# ArduSensor-Pot.net
KiCad netlist of a schematic drawn in EAGLE
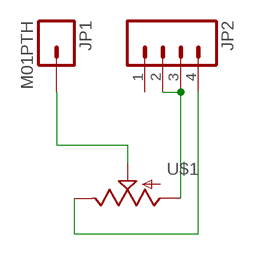
[diagram p0: schematic, sheet 1]

(export (version "E")
  (design (tool "Eeschema 10.0.6"))
  (components
    (comp (ref "JP1")
      (value "M01PTH")
      (footprint "eagle-import:1X01")
      (libsource (lib "eagle-import") (part "M01PTH"))
    )
    (comp (ref "JP2")
      (value "M04PTH")
      (footprint "eagle-import:1X04")
      (libsource (lib "eagle-import") (part "M04PTH"))
    )
    (comp (ref "U$1")
      (value "POT")
      (footprint "eagle-import:ALPS_POT")
      (libsource (lib "eagle-import") (part "POT"))
    )
  )
  (nets
    (net (code "1") (name "Net-(U$1-A)") (class "Default")
      (node (ref "JP2") (pin "2") (pinfunction "2_2") (pintype "passive"))
      (node (ref "JP2") (pin "3") (pinfunction "3_3") (pintype "passive"))
      (node (ref "U$1") (pin "P$3") (pinfunction "A_P$3") (pintype "passive"))
    )
    (net (code "2") (name "Net-(U$1-E)") (class "Default")
      (node (ref "JP2") (pin "4") (pinfunction "4_4") (pintype "passive"))
      (node (ref "U$1") (pin "P$1") (pinfunction "E_P$1") (pintype "passive"))
    )
    (net (code "3") (name "Net-(U$1-S)") (class "Default")
      (node (ref "JP1") (pin "1") (pinfunction "1_1") (pintype "passive"))
      (node (ref "U$1") (pin "P$2") (pinfunction "S_P$2") (pintype "passive"))
    )
    (net (code "4") (name "unconnected-(JP2-Pad1)") (class "Default")
      (node (ref "JP2") (pin "1") (pinfunction "1_1") (pintype "passive"))
    )
  )
)
